# dlp_vco_dualosc_v1_1.net
KiCad netlist of a schematic drawn in EAGLE
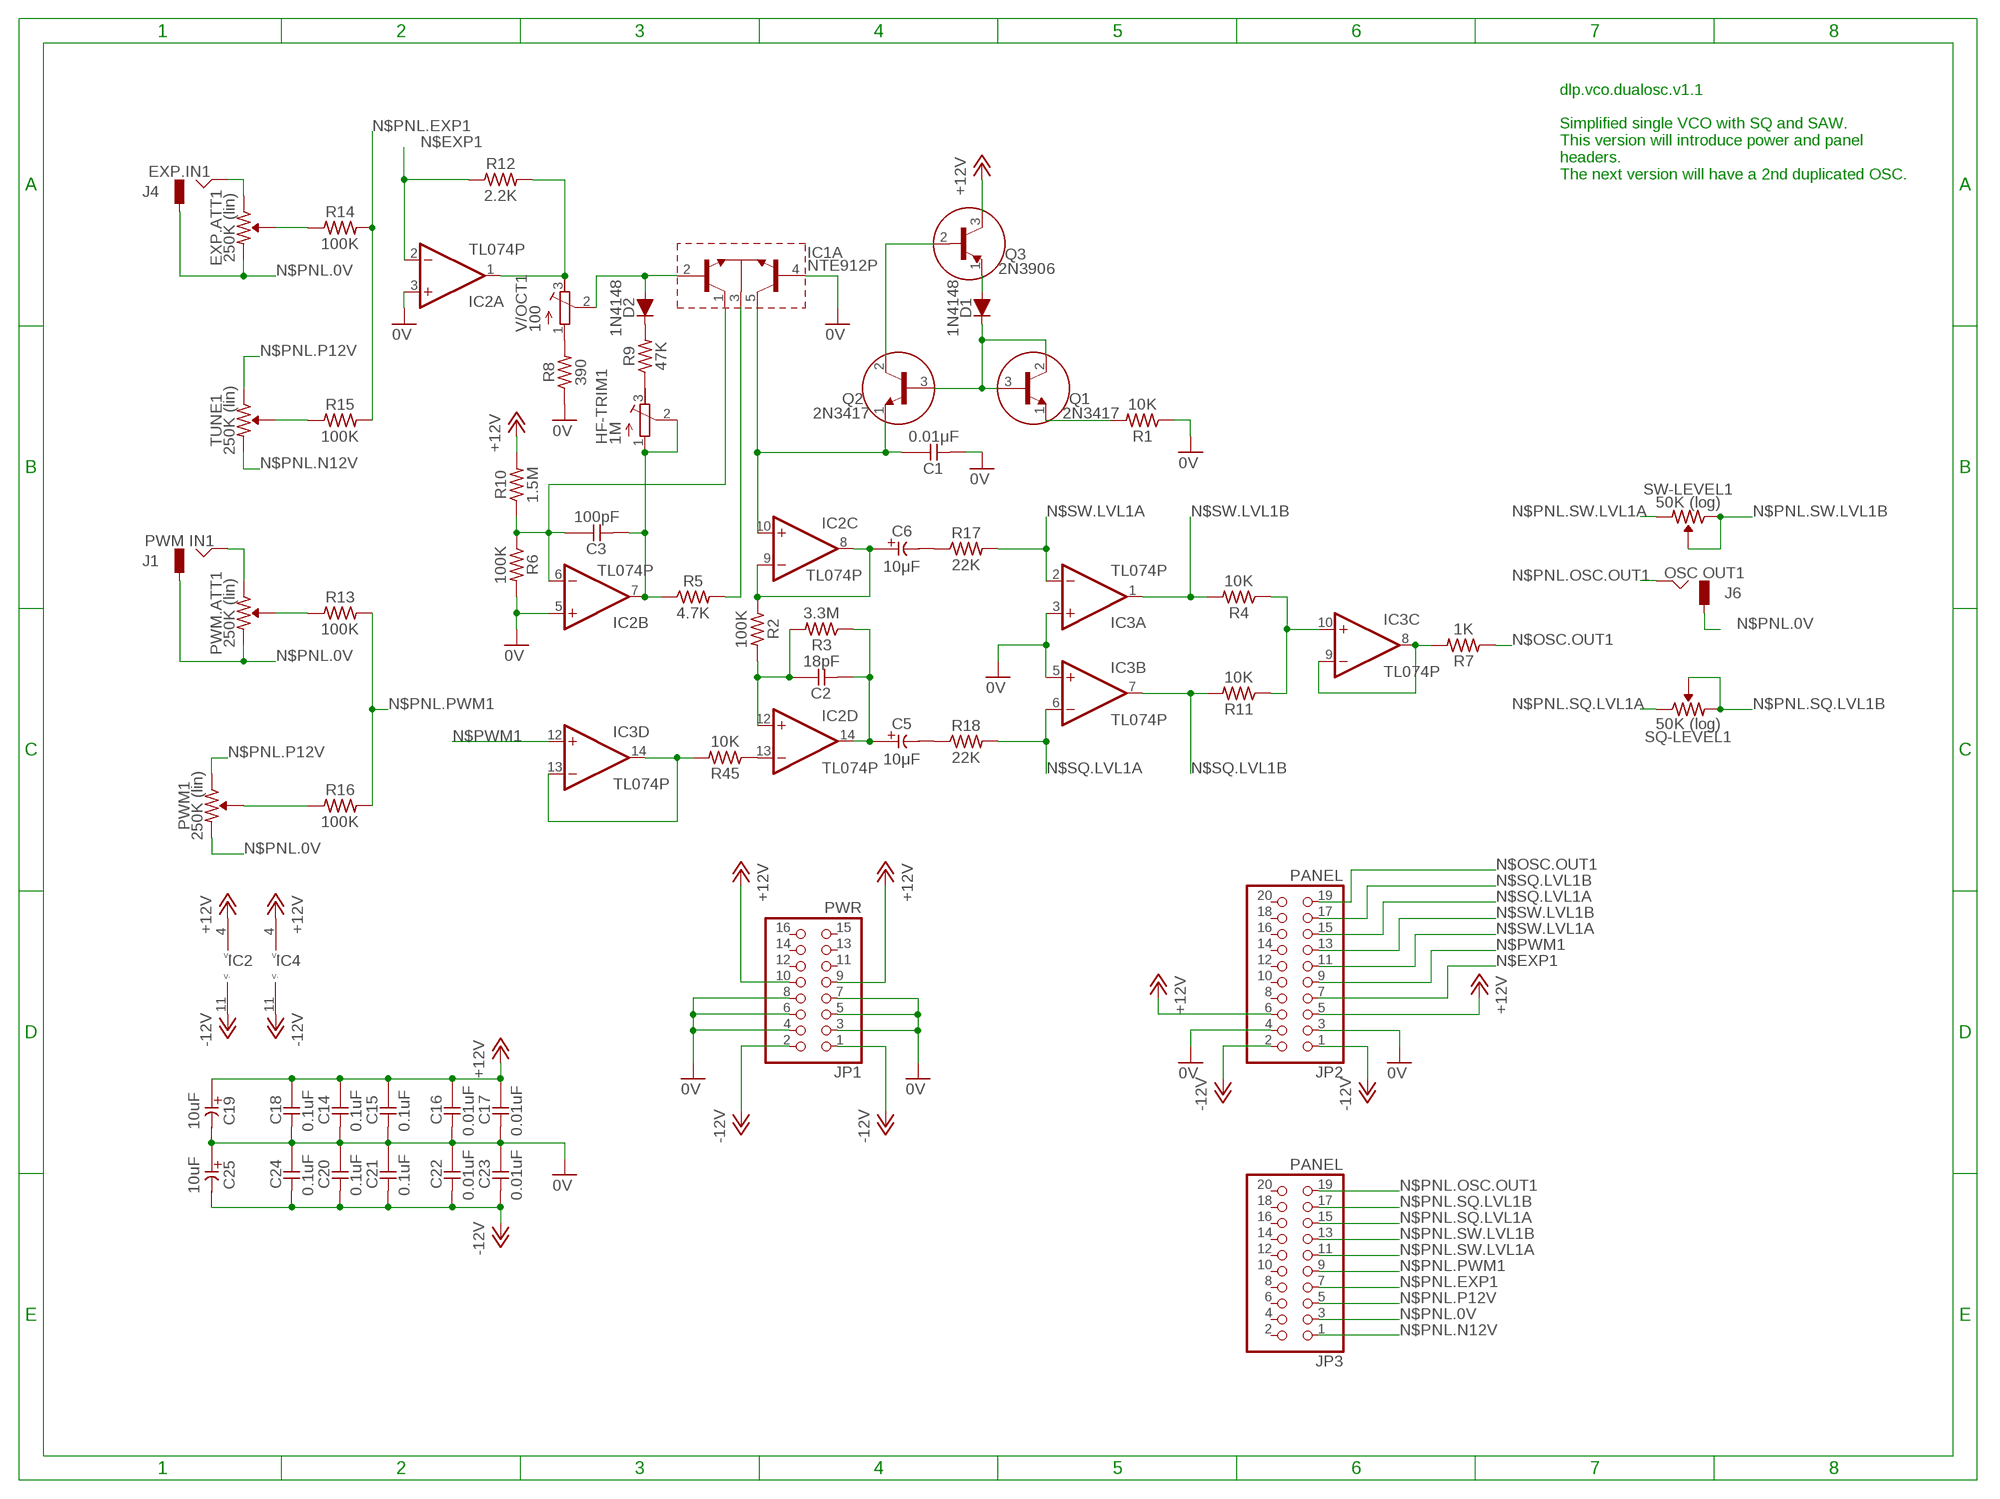
[diagram p0: schematic, sheet 1]

(export (version "E")
  (design (tool "Eeschema 10.0.6"))
  (components
    (comp (ref "C1")
      (value "0.01μF")
      (footprint "eagle-import:C025-024X044")
      (libsource (lib "eagle-import") (part "CC-US025-024X044"))
    )
    (comp (ref "C2")
      (value "18pF")
      (footprint "eagle-import:C025-024X044")
      (libsource (lib "eagle-import") (part "CC-US025-024X044"))
    )
    (comp (ref "C3")
      (value "100pF")
      (footprint "eagle-import:C025-024X044")
      (libsource (lib "eagle-import") (part "CC-US025-024X044"))
    )
    (comp (ref "C5")
      (value "10μF")
      (footprint "eagle-import:E2-5")
      (libsource (lib "eagle-import") (part "CE-USE2-5"))
    )
    (comp (ref "C6")
      (value "10μF")
      (footprint "eagle-import:E2-5")
      (libsource (lib "eagle-import") (part "CE-USE2-5"))
    )
    (comp (ref "C14")
      (value "0.1uF")
      (footprint "eagle-import:C025-024X044")
      (libsource (lib "eagle-import") (part "CC-US025-024X044"))
    )
    (comp (ref "C15")
      (value "0.1uF")
      (footprint "eagle-import:C025-024X044")
      (libsource (lib "eagle-import") (part "CC-US025-024X044"))
    )
    (comp (ref "C16")
      (value "0.01uF")
      (footprint "eagle-import:C025-024X044")
      (libsource (lib "eagle-import") (part "CC-US025-024X044"))
    )
    (comp (ref "C17")
      (value "0.01uF")
      (footprint "eagle-import:C025-024X044")
      (libsource (lib "eagle-import") (part "CC-US025-024X044"))
    )
    (comp (ref "C18")
      (value "0.1uF")
      (footprint "eagle-import:C025-024X044")
      (libsource (lib "eagle-import") (part "CC-US025-024X044"))
    )
    (comp (ref "C19")
      (value "10uF")
      (footprint "eagle-import:E2-5")
      (libsource (lib "eagle-import") (part "CE-USE2-5"))
    )
    (comp (ref "C20")
      (value "0.1uF")
      (footprint "eagle-import:C025-024X044")
      (libsource (lib "eagle-import") (part "CC-US025-024X044"))
    )
    (comp (ref "C21")
      (value "0.1uF")
      (footprint "eagle-import:C025-024X044")
      (libsource (lib "eagle-import") (part "CC-US025-024X044"))
    )
    (comp (ref "C22")
      (value "0.01uF")
      (footprint "eagle-import:C025-024X044")
      (libsource (lib "eagle-import") (part "CC-US025-024X044"))
    )
    (comp (ref "C23")
      (value "0.01uF")
      (footprint "eagle-import:C025-024X044")
      (libsource (lib "eagle-import") (part "CC-US025-024X044"))
    )
    (comp (ref "C24")
      (value "0.1uF")
      (footprint "eagle-import:C025-024X044")
      (libsource (lib "eagle-import") (part "CC-US025-024X044"))
    )
    (comp (ref "C25")
      (value "10uF")
      (footprint "eagle-import:E2-5")
      (libsource (lib "eagle-import") (part "CE-USE2-5"))
    )
    (comp (ref "D1")
      (value "1N4148")
      (footprint "eagle-import:DO35-7")
      (libsource (lib "eagle-import") (part "1N4148"))
    )
    (comp (ref "D2")
      (value "1N4148")
      (footprint "eagle-import:DO35-7")
      (libsource (lib "eagle-import") (part "1N4148"))
    )
    (comp (ref "EXP.ATT1")
      (value "250K (lin)")
      (footprint "eagle-import:R-VAR")
      (libsource (lib "eagle-import") (part "R-VAR"))
    )
    (comp (ref "HF-TRIM1")
      (value "1M")
      (footprint "eagle-import:RTRIM3296Y")
      (libsource (lib "eagle-import") (part "R-TRIMM3296Y"))
    )
    (comp (ref "IC1")
      (value "NTE912P")
      (footprint "eagle-import:DIL14")
      (libsource (lib "eagle-import") (part "NTE912P"))
    )
    (comp (ref "IC2")
      (value "TL074P")
      (footprint "eagle-import:DIL14")
      (libsource (lib "eagle-import") (part "TL074P"))
    )
    (comp (ref "IC3")
      (value "TL074P")
      (footprint "eagle-import:DIL14")
      (libsource (lib "eagle-import") (part "TL074P"))
    )
    (comp (ref "J1")
      (value "PWM IN1")
      (footprint "eagle-import:JACK-M")
      (libsource (lib "eagle-import") (part "JACK-M"))
    )
    (comp (ref "J4")
      (value "EXP.IN1")
      (footprint "eagle-import:JACK-M")
      (libsource (lib "eagle-import") (part "JACK-M"))
    )
    (comp (ref "J6")
      (value "OSC OUT1")
      (footprint "eagle-import:JACK-M")
      (libsource (lib "eagle-import") (part "JACK-M"))
    )
    (comp (ref "JP1")
      (value "PWR")
      (footprint "eagle-import:2X08")
      (libsource (lib "eagle-import") (part "PINHD-2X8"))
    )
    (comp (ref "JP2")
      (value "PANEL")
      (footprint "eagle-import:2X10")
      (libsource (lib "eagle-import") (part "PINHD-2X10"))
    )
    (comp (ref "JP3")
      (value "PANEL")
      (footprint "eagle-import:2X10")
      (libsource (lib "eagle-import") (part "PINHD-2X10"))
    )
    (comp (ref "PWM.ATT1")
      (value "250K (lin)")
      (footprint "eagle-import:R-VAR")
      (libsource (lib "eagle-import") (part "R-VAR"))
    )
    (comp (ref "PWM1")
      (value "250K (lin)")
      (footprint "eagle-import:R-VAR")
      (libsource (lib "eagle-import") (part "R-VAR"))
    )
    (comp (ref "Q1")
      (value "2N3417")
      (footprint "eagle-import:TO92")
      (libsource (lib "eagle-import") (part "2N3417"))
    )
    (comp (ref "Q2")
      (value "2N3417")
      (footprint "eagle-import:TO92")
      (libsource (lib "eagle-import") (part "2N3417"))
    )
    (comp (ref "Q3")
      (value "2N3906")
      (footprint "eagle-import:TO92")
      (libsource (lib "eagle-import") (part "2N3906"))
    )
    (comp (ref "R1")
      (value "10K")
      (footprint "eagle-import:0309_10")
      (libsource (lib "eagle-import") (part "R0309/10"))
    )
    (comp (ref "R2")
      (value "100K")
      (footprint "eagle-import:0309_10")
      (libsource (lib "eagle-import") (part "R0309/10"))
    )
    (comp (ref "R3")
      (value "3.3M")
      (footprint "eagle-import:0309_10")
      (libsource (lib "eagle-import") (part "R0309/10"))
    )
    (comp (ref "R4")
      (value "10K")
      (footprint "eagle-import:0309_10")
      (libsource (lib "eagle-import") (part "R0309/10"))
    )
    (comp (ref "R5")
      (value "4.7K")
      (footprint "eagle-import:0309_10")
      (libsource (lib "eagle-import") (part "R0309/10"))
    )
    (comp (ref "R6")
      (value "100K")
      (footprint "eagle-import:0309_10")
      (libsource (lib "eagle-import") (part "R0309/10"))
    )
    (comp (ref "R7")
      (value "1K")
      (footprint "eagle-import:0309_10")
      (libsource (lib "eagle-import") (part "R0309/10"))
    )
    (comp (ref "R8")
      (value "390")
      (footprint "eagle-import:0309_10")
      (libsource (lib "eagle-import") (part "R0309/10"))
    )
    (comp (ref "R9")
      (value "47K")
      (footprint "eagle-import:0309_10")
      (libsource (lib "eagle-import") (part "R0309/10"))
    )
    (comp (ref "R10")
      (value "1.5M")
      (footprint "eagle-import:0309_10")
      (libsource (lib "eagle-import") (part "R0309/10"))
    )
    (comp (ref "R11")
      (value "10K")
      (footprint "eagle-import:0309_10")
      (libsource (lib "eagle-import") (part "R0309/10"))
    )
    (comp (ref "R12")
      (value "2.2K")
      (footprint "eagle-import:0309_10")
      (libsource (lib "eagle-import") (part "R0309/10"))
    )
    (comp (ref "R13")
      (value "100K")
      (footprint "eagle-import:0309_10")
      (libsource (lib "eagle-import") (part "R0309/10"))
    )
    (comp (ref "R14")
      (value "100K")
      (footprint "eagle-import:0309_10")
      (libsource (lib "eagle-import") (part "R0309/10"))
    )
    (comp (ref "R15")
      (value "100K")
      (footprint "eagle-import:0309_10")
      (libsource (lib "eagle-import") (part "R0309/10"))
    )
    (comp (ref "R16")
      (value "100K")
      (footprint "eagle-import:0309_10")
      (libsource (lib "eagle-import") (part "R0309/10"))
    )
    (comp (ref "R17")
      (value "22K")
      (footprint "eagle-import:0309_10")
      (libsource (lib "eagle-import") (part "R0309/10"))
    )
    (comp (ref "R18")
      (value "22K")
      (footprint "eagle-import:0309_10")
      (libsource (lib "eagle-import") (part "R0309/10"))
    )
    (comp (ref "R45")
      (value "10K")
      (footprint "eagle-import:0309_10")
      (libsource (lib "eagle-import") (part "R0309/10"))
    )
    (comp (ref "SQ-LEVEL1")
      (value "50K (log)")
      (footprint "eagle-import:R-VAR")
      (libsource (lib "eagle-import") (part "R-VAR"))
    )
    (comp (ref "SW-LEVEL1")
      (value "50K (log)")
      (footprint "eagle-import:R-VAR")
      (libsource (lib "eagle-import") (part "R-VAR"))
    )
    (comp (ref "TUNE1")
      (value "250K (lin)")
      (footprint "eagle-import:R-VAR")
      (libsource (lib "eagle-import") (part "R-VAR"))
    )
    (comp (ref "V/OCT1")
      (value "100")
      (footprint "eagle-import:RTRIM3296Y")
      (libsource (lib "eagle-import") (part "R-TRIMM3296Y"))
    )
  )
  (nets
    (net (code "1") (name "+12V") (class "Default")
      (node (ref "C14") (pin "1") (pinfunction "1_1") (pintype "passive"))
      (node (ref "C15") (pin "1") (pinfunction "1_1") (pintype "passive"))
      (node (ref "C16") (pin "1") (pinfunction "1_1") (pintype "passive"))
      (node (ref "C17") (pin "1") (pinfunction "1_1") (pintype "passive"))
      (node (ref "C18") (pin "1") (pinfunction "1_1") (pintype "passive"))
      (node (ref "C19") (pin "+") (pinfunction "+_+") (pintype "passive"))
      (node (ref "IC2") (pin "4") (pinfunction "V+_4") (pintype "power_in"))
      (node (ref "IC3") (pin "4") (pinfunction "V+_4") (pintype "power_in"))
      (node (ref "JP1") (pin "10") (pinfunction "10_10") (pintype "passive"))
      (node (ref "JP1") (pin "9") (pinfunction "9_9") (pintype "passive"))
      (node (ref "JP2") (pin "5") (pinfunction "5_5") (pintype "passive"))
      (node (ref "JP2") (pin "6") (pinfunction "6_6") (pintype "passive"))
      (node (ref "Q3") (pin "3") (pinfunction "C_3") (pintype "passive"))
      (node (ref "R10") (pin "2") (pinfunction "2_2") (pintype "passive"))
    )
    (net (code "2") (name "-12V") (class "Default")
      (node (ref "C20") (pin "2") (pinfunction "2_2") (pintype "passive"))
      (node (ref "C21") (pin "2") (pinfunction "2_2") (pintype "passive"))
      (node (ref "C22") (pin "2") (pinfunction "2_2") (pintype "passive"))
      (node (ref "C23") (pin "2") (pinfunction "2_2") (pintype "passive"))
      (node (ref "C24") (pin "2") (pinfunction "2_2") (pintype "passive"))
      (node (ref "C25") (pin "-") (pinfunction "-_-") (pintype "passive"))
      (node (ref "IC2") (pin "11") (pinfunction "V-_11") (pintype "power_in"))
      (node (ref "IC3") (pin "11") (pinfunction "V-_11") (pintype "power_in"))
      (node (ref "JP1") (pin "1") (pinfunction "1_1") (pintype "passive"))
      (node (ref "JP1") (pin "2") (pinfunction "2_2") (pintype "passive"))
      (node (ref "JP2") (pin "1") (pinfunction "1_1") (pintype "passive"))
      (node (ref "JP2") (pin "2") (pinfunction "2_2") (pintype "passive"))
    )
    (net (code "3") (name "/N$EXP1") (class "Default")
      (node (ref "IC2") (pin "2") (pinfunction "-IN_2") (pintype "input"))
      (node (ref "JP2") (pin "7") (pinfunction "7_7") (pintype "passive"))
      (node (ref "R12") (pin "1") (pinfunction "1_1") (pintype "passive"))
    )
    (net (code "4") (name "/N$OSC.OUT1") (class "Default")
      (node (ref "JP2") (pin "19") (pinfunction "19_19") (pintype "passive"))
      (node (ref "R7") (pin "1") (pinfunction "1_1") (pintype "passive"))
    )
    (net (code "5") (name "/N$PNL.0V") (class "Default")
      (node (ref "EXP.ATT1") (pin "R2") (pinfunction "2_R2") (pintype "passive"))
      (node (ref "J1") (pin "GND") (pinfunction "GND_GND") (pintype "bidirectional"))
      (node (ref "J4") (pin "GND") (pinfunction "GND_GND") (pintype "bidirectional"))
      (node (ref "J6") (pin "GND") (pinfunction "GND_GND") (pintype "bidirectional"))
      (node (ref "JP3") (pin "3") (pinfunction "3_3") (pintype "passive"))
      (node (ref "PWM.ATT1") (pin "R2") (pinfunction "2_R2") (pintype "passive"))
      (node (ref "PWM1") (pin "R2") (pinfunction "2_R2") (pintype "passive"))
    )
    (net (code "6") (name "/N$PNL.EXP1") (class "Default")
      (node (ref "JP3") (pin "7") (pinfunction "7_7") (pintype "passive"))
      (node (ref "R14") (pin "2") (pinfunction "2_2") (pintype "passive"))
      (node (ref "R15") (pin "2") (pinfunction "2_2") (pintype "passive"))
    )
    (net (code "7") (name "/N$PNL.N12V") (class "Default")
      (node (ref "JP3") (pin "1") (pinfunction "1_1") (pintype "passive"))
      (node (ref "TUNE1") (pin "R2") (pinfunction "2_R2") (pintype "passive"))
    )
    (net (code "8") (name "/N$PNL.OSC.OUT1") (class "Default")
      (node (ref "J6") (pin "HOT") (pinfunction "HOT_HOT") (pintype "bidirectional"))
      (node (ref "JP3") (pin "19") (pinfunction "19_19") (pintype "passive"))
    )
    (net (code "9") (name "/N$PNL.P12V") (class "Default")
      (node (ref "JP3") (pin "5") (pinfunction "5_5") (pintype "passive"))
      (node (ref "PWM1") (pin "R1") (pinfunction "1_R1") (pintype "passive"))
      (node (ref "TUNE1") (pin "R1") (pinfunction "1_R1") (pintype "passive"))
    )
    (net (code "10") (name "/N$PNL.PWM1") (class "Default")
      (node (ref "JP3") (pin "9") (pinfunction "9_9") (pintype "passive"))
      (node (ref "R13") (pin "2") (pinfunction "2_2") (pintype "passive"))
      (node (ref "R16") (pin "2") (pinfunction "2_2") (pintype "passive"))
    )
    (net (code "11") (name "/N$PNL.SQ.LVL1A") (class "Default")
      (node (ref "JP3") (pin "15") (pinfunction "15_15") (pintype "passive"))
      (node (ref "SQ-LEVEL1") (pin "R1") (pinfunction "1_R1") (pintype "passive"))
    )
    (net (code "12") (name "/N$PNL.SQ.LVL1B") (class "Default")
      (node (ref "JP3") (pin "17") (pinfunction "17_17") (pintype "passive"))
      (node (ref "SQ-LEVEL1") (pin "R2") (pinfunction "2_R2") (pintype "passive"))
      (node (ref "SQ-LEVEL1") (pin "VAR") (pinfunction "P$1_VAR") (pintype "passive"))
    )
    (net (code "13") (name "/N$PNL.SW.LVL1A") (class "Default")
      (node (ref "JP3") (pin "11") (pinfunction "11_11") (pintype "passive"))
      (node (ref "SW-LEVEL1") (pin "R2") (pinfunction "2_R2") (pintype "passive"))
    )
    (net (code "14") (name "/N$PNL.SW.LVL1B") (class "Default")
      (node (ref "JP3") (pin "13") (pinfunction "13_13") (pintype "passive"))
      (node (ref "SW-LEVEL1") (pin "R1") (pinfunction "1_R1") (pintype "passive"))
      (node (ref "SW-LEVEL1") (pin "VAR") (pinfunction "P$1_VAR") (pintype "passive"))
    )
    (net (code "15") (name "/N$PWM1") (class "Default")
      (node (ref "IC3") (pin "12") (pinfunction "+IN_12") (pintype "input"))
      (node (ref "JP2") (pin "9") (pinfunction "9_9") (pintype "passive"))
    )
    (net (code "16") (name "/N$SQ.LVL1A") (class "Default")
      (node (ref "IC3") (pin "6") (pinfunction "-IN_6") (pintype "input"))
      (node (ref "JP2") (pin "15") (pinfunction "15_15") (pintype "passive"))
      (node (ref "R18") (pin "2") (pinfunction "2_2") (pintype "passive"))
    )
    (net (code "17") (name "/N$SQ.LVL1B") (class "Default")
      (node (ref "IC3") (pin "7") (pinfunction "OUT_7") (pintype "output"))
      (node (ref "JP2") (pin "17") (pinfunction "17_17") (pintype "passive"))
      (node (ref "R11") (pin "2") (pinfunction "2_2") (pintype "passive"))
    )
    (net (code "18") (name "/N$SW.LVL1A") (class "Default")
      (node (ref "IC3") (pin "2") (pinfunction "-IN_2") (pintype "input"))
      (node (ref "JP2") (pin "11") (pinfunction "11_11") (pintype "passive"))
      (node (ref "R17") (pin "2") (pinfunction "2_2") (pintype "passive"))
    )
    (net (code "19") (name "/N$SW.LVL1B") (class "Default")
      (node (ref "IC3") (pin "1") (pinfunction "OUT_1") (pintype "output"))
      (node (ref "JP2") (pin "13") (pinfunction "13_13") (pintype "passive"))
      (node (ref "R4") (pin "2") (pinfunction "2_2") (pintype "passive"))
    )
    (net (code "20") (name "0V") (class "Default")
      (node (ref "C1") (pin "2") (pinfunction "2_2") (pintype "passive"))
      (node (ref "C14") (pin "2") (pinfunction "2_2") (pintype "passive"))
      (node (ref "C15") (pin "2") (pinfunction "2_2") (pintype "passive"))
      (node (ref "C16") (pin "2") (pinfunction "2_2") (pintype "passive"))
      (node (ref "C17") (pin "2") (pinfunction "2_2") (pintype "passive"))
      (node (ref "C18") (pin "2") (pinfunction "2_2") (pintype "passive"))
      (node (ref "C19") (pin "-") (pinfunction "-_-") (pintype "passive"))
      (node (ref "C20") (pin "1") (pinfunction "1_1") (pintype "passive"))
      (node (ref "C21") (pin "1") (pinfunction "1_1") (pintype "passive"))
      (node (ref "C22") (pin "1") (pinfunction "1_1") (pintype "passive"))
      (node (ref "C23") (pin "1") (pinfunction "1_1") (pintype "passive"))
      (node (ref "C24") (pin "1") (pinfunction "1_1") (pintype "passive"))
      (node (ref "C25") (pin "+") (pinfunction "+_+") (pintype "passive"))
      (node (ref "IC1") (pin "4") (pinfunction "B3_4") (pintype "passive"))
      (node (ref "IC2") (pin "3") (pinfunction "+IN_3") (pintype "input"))
      (node (ref "IC2") (pin "5") (pinfunction "+IN_5") (pintype "input"))
      (node (ref "IC3") (pin "3") (pinfunction "+IN_3") (pintype "input"))
      (node (ref "IC3") (pin "5") (pinfunction "+IN_5") (pintype "input"))
      (node (ref "JP1") (pin "3") (pinfunction "3_3") (pintype "passive"))
      (node (ref "JP1") (pin "4") (pinfunction "4_4") (pintype "passive"))
      (node (ref "JP1") (pin "5") (pinfunction "5_5") (pintype "passive"))
      (node (ref "JP1") (pin "6") (pinfunction "6_6") (pintype "passive"))
      (node (ref "JP1") (pin "7") (pinfunction "7_7") (pintype "passive"))
      (node (ref "JP1") (pin "8") (pinfunction "8_8") (pintype "passive"))
      (node (ref "JP2") (pin "3") (pinfunction "3_3") (pintype "passive"))
      (node (ref "JP2") (pin "4") (pinfunction "4_4") (pintype "passive"))
      (node (ref "R1") (pin "1") (pinfunction "1_1") (pintype "passive"))
      (node (ref "R6") (pin "2") (pinfunction "2_2") (pintype "passive"))
      (node (ref "R8") (pin "1") (pinfunction "1_1") (pintype "passive"))
    )
    (net (code "21") (name "Net-(C5-Pad-)") (class "Default")
      (node (ref "C5") (pin "-") (pinfunction "-_-") (pintype "passive"))
      (node (ref "R18") (pin "1") (pinfunction "1_1") (pintype "passive"))
    )
    (net (code "22") (name "Net-(C6-Pad-)") (class "Default")
      (node (ref "C6") (pin "-") (pinfunction "-_-") (pintype "passive"))
      (node (ref "R17") (pin "1") (pinfunction "1_1") (pintype "passive"))
    )
    (net (code "23") (name "Net-(D2-PadC)") (class "Default")
      (node (ref "D2") (pin "C") (pinfunction "C_C") (pintype "passive"))
      (node (ref "R9") (pin "2") (pinfunction "2_2") (pintype "passive"))
    )
    (net (code "24") (name "Net-(EXP.ATT1-1)") (class "Default")
      (node (ref "EXP.ATT1") (pin "R1") (pinfunction "1_R1") (pintype "passive"))
      (node (ref "J4") (pin "HOT") (pinfunction "HOT_HOT") (pintype "bidirectional"))
    )
    (net (code "25") (name "Net-(EXP.ATT1-P$1)") (class "Default")
      (node (ref "EXP.ATT1") (pin "VAR") (pinfunction "P$1_VAR") (pintype "passive"))
      (node (ref "R14") (pin "1") (pinfunction "1_1") (pintype "passive"))
    )
    (net (code "26") (name "Net-(HF-TRIM1-A)") (class "Default")
      (node (ref "C3") (pin "2") (pinfunction "2_2") (pintype "passive"))
      (node (ref "HF-TRIM1") (pin "1") (pinfunction "A_1") (pintype "passive"))
      (node (ref "HF-TRIM1") (pin "2") (pinfunction "S_2") (pintype "passive"))
      (node (ref "IC2") (pin "7") (pinfunction "OUT_7") (pintype "output"))
      (node (ref "R5") (pin "1") (pinfunction "1_1") (pintype "passive"))
    )
    (net (code "27") (name "Net-(HF-TRIM1-E)") (class "Default")
      (node (ref "HF-TRIM1") (pin "3") (pinfunction "E_3") (pintype "passive"))
      (node (ref "R9") (pin "1") (pinfunction "1_1") (pintype "passive"))
    )
    (net (code "28") (name "Net-(IC1A-B1)") (class "Default")
      (node (ref "D2") (pin "A") (pinfunction "A_A") (pintype "passive"))
      (node (ref "IC1") (pin "2") (pinfunction "B1_2") (pintype "passive"))
      (node (ref "V/OCT1") (pin "2") (pinfunction "S_2") (pintype "passive"))
    )
    (net (code "29") (name "Net-(IC1A-C1)") (class "Default")
      (node (ref "C3") (pin "1") (pinfunction "1_1") (pintype "passive"))
      (node (ref "IC1") (pin "1") (pinfunction "C1_1") (pintype "passive"))
      (node (ref "IC2") (pin "6") (pinfunction "-IN_6") (pintype "input"))
      (node (ref "R10") (pin "1") (pinfunction "1_1") (pintype "passive"))
      (node (ref "R6") (pin "1") (pinfunction "1_1") (pintype "passive"))
    )
    (net (code "30") (name "Net-(IC1A-C3)") (class "Default")
      (node (ref "C1") (pin "1") (pinfunction "1_1") (pintype "passive"))
      (node (ref "IC1") (pin "5") (pinfunction "C3_5") (pintype "passive"))
      (node (ref "IC2") (pin "10") (pinfunction "+IN_10") (pintype "input"))
      (node (ref "Q2") (pin "1") (pinfunction "E_1") (pintype "passive"))
    )
    (net (code "31") (name "Net-(IC1A-E)") (class "Default")
      (node (ref "IC1") (pin "3") (pinfunction "E_3") (pintype "passive"))
      (node (ref "R5") (pin "2") (pinfunction "2_2") (pintype "passive"))
    )
    (net (code "32") (name "Net-(IC2A-OUT)") (class "Default")
      (node (ref "IC2") (pin "1") (pinfunction "OUT_1") (pintype "output"))
      (node (ref "R12") (pin "2") (pinfunction "2_2") (pintype "passive"))
      (node (ref "V/OCT1") (pin "3") (pinfunction "E_3") (pintype "passive"))
    )
    (net (code "33") (name "Net-(IC2C--IN)") (class "Default")
      (node (ref "C6") (pin "+") (pinfunction "+_+") (pintype "passive"))
      (node (ref "IC2") (pin "8") (pinfunction "OUT_8") (pintype "output"))
      (node (ref "IC2") (pin "9") (pinfunction "-IN_9") (pintype "input"))
      (node (ref "R2") (pin "1") (pinfunction "1_1") (pintype "passive"))
    )
    (net (code "34") (name "Net-(IC2D-+IN)") (class "Default")
      (node (ref "C2") (pin "1") (pinfunction "1_1") (pintype "passive"))
      (node (ref "IC2") (pin "12") (pinfunction "+IN_12") (pintype "input"))
      (node (ref "R2") (pin "2") (pinfunction "2_2") (pintype "passive"))
      (node (ref "R3") (pin "2") (pinfunction "2_2") (pintype "passive"))
    )
    (net (code "35") (name "Net-(IC2D--IN)") (class "Default")
      (node (ref "IC2") (pin "13") (pinfunction "-IN_13") (pintype "input"))
      (node (ref "R45") (pin "1") (pinfunction "1_1") (pintype "passive"))
    )
    (net (code "36") (name "Net-(IC2D-OUT)") (class "Default")
      (node (ref "C2") (pin "2") (pinfunction "2_2") (pintype "passive"))
      (node (ref "C5") (pin "+") (pinfunction "+_+") (pintype "passive"))
      (node (ref "IC2") (pin "14") (pinfunction "OUT_14") (pintype "output"))
      (node (ref "R3") (pin "1") (pinfunction "1_1") (pintype "passive"))
    )
    (net (code "37") (name "Net-(IC3C-+IN)") (class "Default")
      (node (ref "IC3") (pin "10") (pinfunction "+IN_10") (pintype "input"))
      (node (ref "R11") (pin "1") (pinfunction "1_1") (pintype "passive"))
      (node (ref "R4") (pin "1") (pinfunction "1_1") (pintype "passive"))
    )
    (net (code "38") (name "Net-(IC3C--IN)") (class "Default")
      (node (ref "IC3") (pin "8") (pinfunction "OUT_8") (pintype "output"))
      (node (ref "IC3") (pin "9") (pinfunction "-IN_9") (pintype "input"))
      (node (ref "R7") (pin "2") (pinfunction "2_2") (pintype "passive"))
    )
    (net (code "39") (name "Net-(IC3D--IN)") (class "Default")
      (node (ref "IC3") (pin "13") (pinfunction "-IN_13") (pintype "input"))
      (node (ref "IC3") (pin "14") (pinfunction "OUT_14") (pintype "output"))
      (node (ref "R45") (pin "2") (pinfunction "2_2") (pintype "passive"))
    )
    (net (code "40") (name "Net-(PWM.ATT1-1)") (class "Default")
      (node (ref "J1") (pin "HOT") (pinfunction "HOT_HOT") (pintype "bidirectional"))
      (node (ref "PWM.ATT1") (pin "R1") (pinfunction "1_R1") (pintype "passive"))
    )
    (net (code "41") (name "Net-(PWM.ATT1-P$1)") (class "Default")
      (node (ref "PWM.ATT1") (pin "VAR") (pinfunction "P$1_VAR") (pintype "passive"))
      (node (ref "R13") (pin "1") (pinfunction "1_1") (pintype "passive"))
    )
    (net (code "42") (name "Net-(PWM1-P$1)") (class "Default")
      (node (ref "PWM1") (pin "VAR") (pinfunction "P$1_VAR") (pintype "passive"))
      (node (ref "R16") (pin "1") (pinfunction "1_1") (pintype "passive"))
    )
    (net (code "43") (name "Net-(Q1-B)") (class "Default")
      (node (ref "D1") (pin "C") (pinfunction "C_C") (pintype "passive"))
      (node (ref "Q1") (pin "2") (pinfunction "C_2") (pintype "passive"))
      (node (ref "Q1") (pin "3") (pinfunction "B_3") (pintype "passive"))
      (node (ref "Q2") (pin "3") (pinfunction "B_3") (pintype "passive"))
    )
    (net (code "44") (name "Net-(Q1-E)") (class "Default")
      (node (ref "Q1") (pin "1") (pinfunction "E_1") (pintype "passive"))
      (node (ref "R1") (pin "2") (pinfunction "2_2") (pintype "passive"))
    )
    (net (code "45") (name "Net-(Q2-C)") (class "Default")
      (node (ref "Q2") (pin "2") (pinfunction "C_2") (pintype "passive"))
      (node (ref "Q3") (pin "2") (pinfunction "B_2") (pintype "passive"))
    )
    (net (code "46") (name "Net-(Q3-E)") (class "Default")
      (node (ref "D1") (pin "A") (pinfunction "A_A") (pintype "passive"))
      (node (ref "Q3") (pin "1") (pinfunction "E_1") (pintype "passive"))
    )
    (net (code "47") (name "Net-(TUNE1-P$1)") (class "Default")
      (node (ref "R15") (pin "1") (pinfunction "1_1") (pintype "passive"))
      (node (ref "TUNE1") (pin "VAR") (pinfunction "P$1_VAR") (pintype "passive"))
    )
    (net (code "48") (name "Net-(V/OCT1-A)") (class "Default")
      (node (ref "R8") (pin "2") (pinfunction "2_2") (pintype "passive"))
      (node (ref "V/OCT1") (pin "1") (pinfunction "A_1") (pintype "passive"))
    )
    (net (code "49") (name "unconnected-(JP1-Pad11)") (class "Default")
      (node (ref "JP1") (pin "11") (pinfunction "11_11") (pintype "passive"))
    )
    (net (code "50") (name "unconnected-(JP1-Pad12)") (class "Default")
      (node (ref "JP1") (pin "12") (pinfunction "12_12") (pintype "passive"))
    )
    (net (code "51") (name "unconnected-(JP1-Pad13)") (class "Default")
      (node (ref "JP1") (pin "13") (pinfunction "13_13") (pintype "passive"))
    )
    (net (code "52") (name "unconnected-(JP1-Pad14)") (class "Default")
      (node (ref "JP1") (pin "14") (pinfunction "14_14") (pintype "passive"))
    )
    (net (code "53") (name "unconnected-(JP1-Pad15)") (class "Default")
      (node (ref "JP1") (pin "15") (pinfunction "15_15") (pintype "passive"))
    )
    (net (code "54") (name "unconnected-(JP1-Pad16)") (class "Default")
      (node (ref "JP1") (pin "16") (pinfunction "16_16") (pintype "passive"))
    )
    (net (code "55") (name "unconnected-(JP2-Pad8)") (class "Default")
      (node (ref "JP2") (pin "8") (pinfunction "8_8") (pintype "passive"))
    )
    (net (code "56") (name "unconnected-(JP2-Pad10)") (class "Default")
      (node (ref "JP2") (pin "10") (pinfunction "10_10") (pintype "passive"))
    )
    (net (code "57") (name "unconnected-(JP2-Pad12)") (class "Default")
      (node (ref "JP2") (pin "12") (pinfunction "12_12") (pintype "passive"))
    )
    (net (code "58") (name "unconnected-(JP2-Pad14)") (class "Default")
      (node (ref "JP2") (pin "14") (pinfunction "14_14") (pintype "passive"))
    )
    (net (code "59") (name "unconnected-(JP2-Pad16)") (class "Default")
      (node (ref "JP2") (pin "16") (pinfunction "16_16") (pintype "passive"))
    )
    (net (code "60") (name "unconnected-(JP2-Pad18)") (class "Default")
      (node (ref "JP2") (pin "18") (pinfunction "18_18") (pintype "passive"))
    )
    (net (code "61") (name "unconnected-(JP2-Pad20)") (class "Default")
      (node (ref "JP2") (pin "20") (pinfunction "20_20") (pintype "passive"))
    )
    (net (code "62") (name "unconnected-(JP3-Pad2)") (class "Default")
      (node (ref "JP3") (pin "2") (pinfunction "2_2") (pintype "passive"))
    )
    (net (code "63") (name "unconnected-(JP3-Pad4)") (class "Default")
      (node (ref "JP3") (pin "4") (pinfunction "4_4") (pintype "passive"))
    )
    (net (code "64") (name "unconnected-(JP3-Pad6)") (class "Default")
      (node (ref "JP3") (pin "6") (pinfunction "6_6") (pintype "passive"))
    )
    (net (code "65") (name "unconnected-(JP3-Pad8)") (class "Default")
      (node (ref "JP3") (pin "8") (pinfunction "8_8") (pintype "passive"))
    )
    (net (code "66") (name "unconnected-(JP3-Pad10)") (class "Default")
      (node (ref "JP3") (pin "10") (pinfunction "10_10") (pintype "passive"))
    )
    (net (code "67") (name "unconnected-(JP3-Pad12)") (class "Default")
      (node (ref "JP3") (pin "12") (pinfunction "12_12") (pintype "passive"))
    )
    (net (code "68") (name "unconnected-(JP3-Pad14)") (class "Default")
      (node (ref "JP3") (pin "14") (pinfunction "14_14") (pintype "passive"))
    )
    (net (code "69") (name "unconnected-(JP3-Pad16)") (class "Default")
      (node (ref "JP3") (pin "16") (pinfunction "16_16") (pintype "passive"))
    )
    (net (code "70") (name "unconnected-(JP3-Pad18)") (class "Default")
      (node (ref "JP3") (pin "18") (pinfunction "18_18") (pintype "passive"))
    )
    (net (code "71") (name "unconnected-(JP3-Pad20)") (class "Default")
      (node (ref "JP3") (pin "20") (pinfunction "20_20") (pintype "passive"))
    )
  )
)
